# micro-xum1541.net
KiCad netlist of a schematic drawn in EAGLE
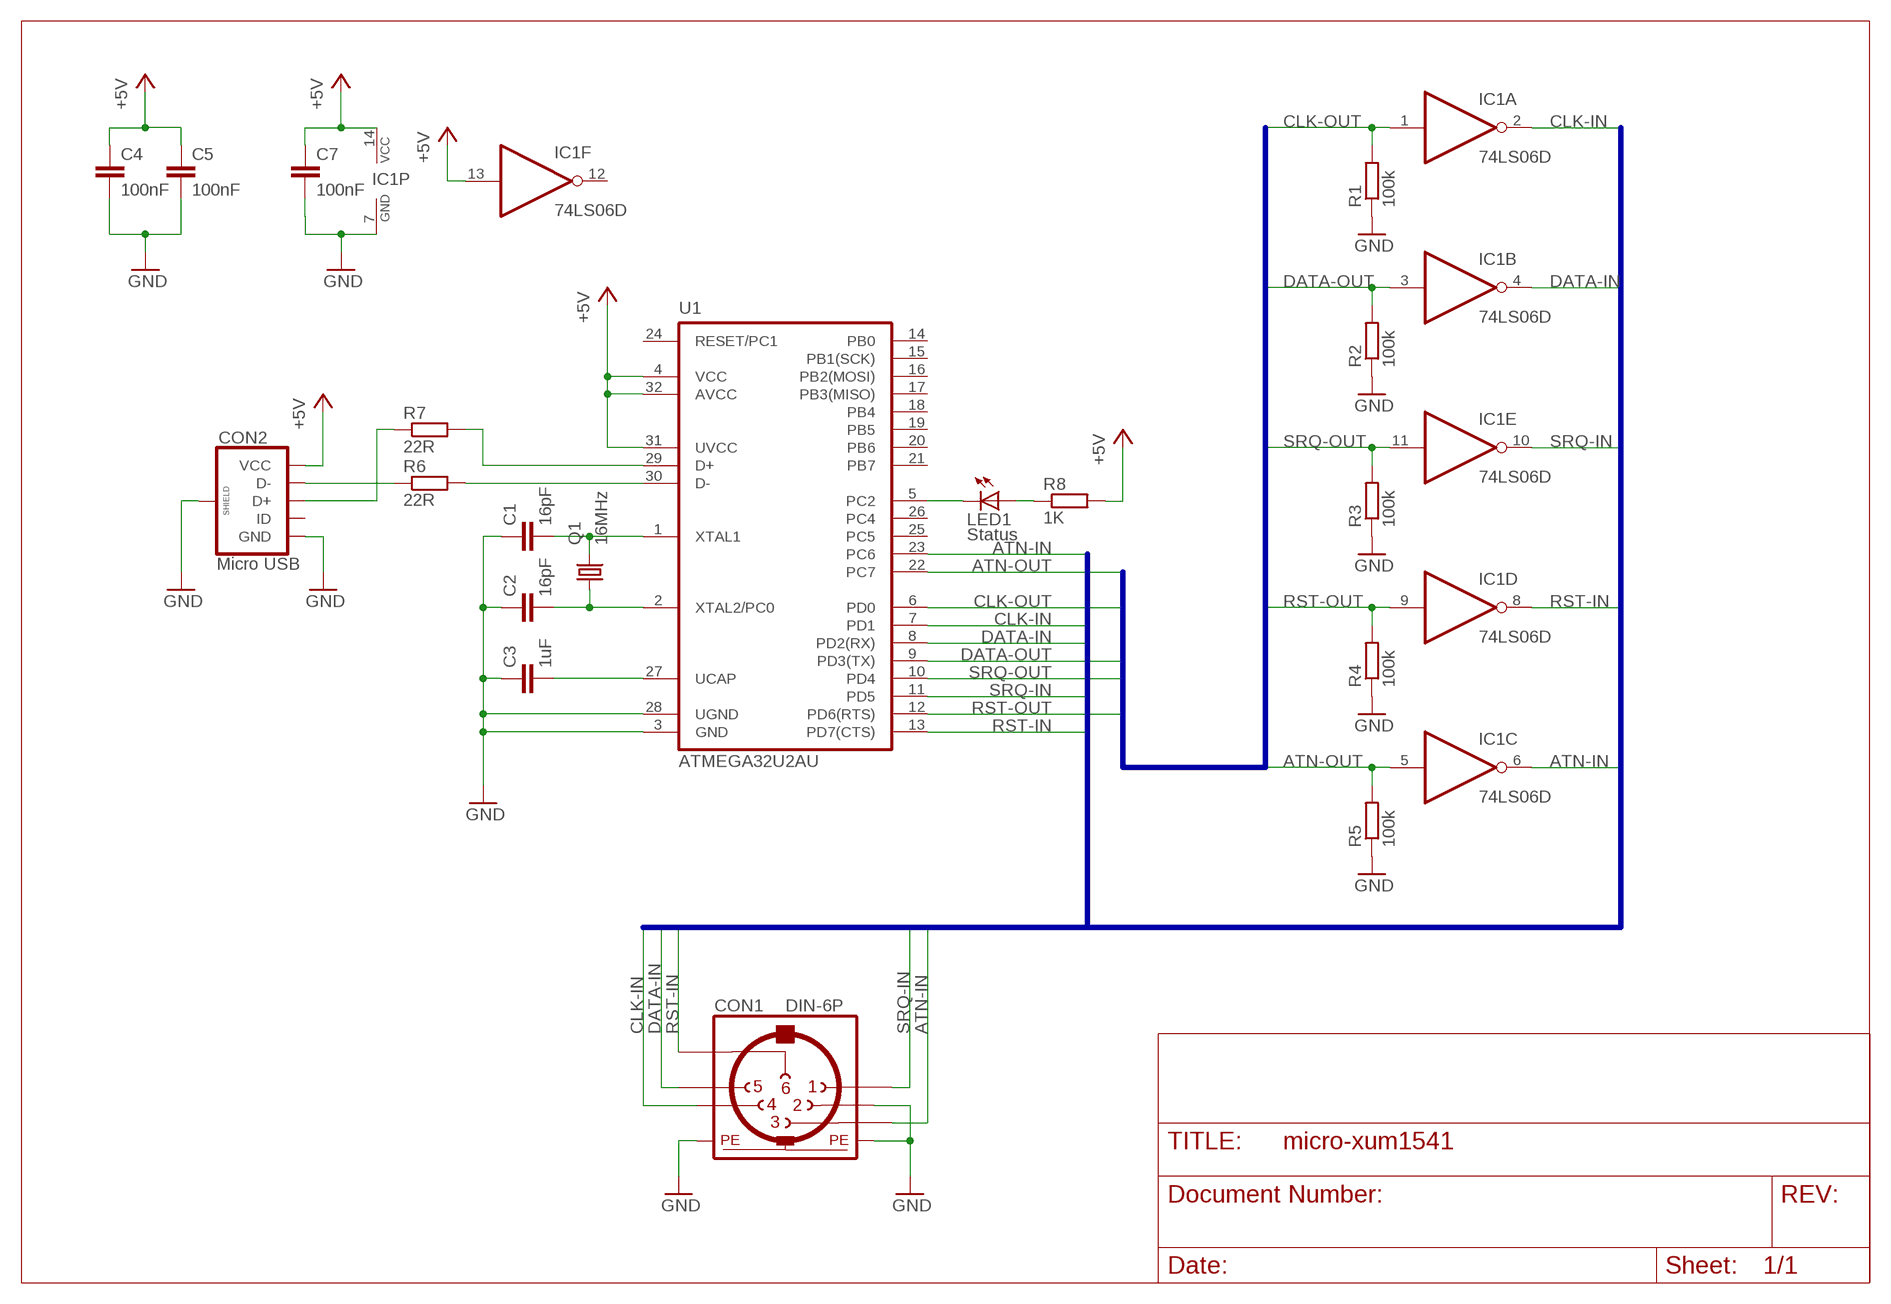
[diagram p0: schematic, sheet 1]

(export (version "E")
  (design (tool "Eeschema 10.0.6"))
  (components
    (comp (ref "C1")
      (value "16pF")
      (footprint "eagle-import:C0603K")
      (libsource (lib "eagle-import") (part "C-EUC0603K"))
    )
    (comp (ref "C2")
      (value "16pF")
      (footprint "eagle-import:C0603K")
      (libsource (lib "eagle-import") (part "C-EUC0603K"))
    )
    (comp (ref "C3")
      (value "1uF")
      (footprint "eagle-import:C0603")
      (libsource (lib "eagle-import") (part "C-EUC0603"))
    )
    (comp (ref "C4")
      (value "100nF")
      (footprint "eagle-import:C0603")
      (libsource (lib "eagle-import") (part "C-EUC0603"))
    )
    (comp (ref "C5")
      (value "100nF")
      (footprint "eagle-import:C0603")
      (libsource (lib "eagle-import") (part "C-EUC0603"))
    )
    (comp (ref "C7")
      (value "100nF")
      (footprint "eagle-import:C0603K")
      (libsource (lib "eagle-import") (part "C-EUC0603K"))
    )
    (comp (ref "CON1")
      (value "DIN-6P")
      (footprint "eagle-import:6P")
      (fields (field (name "SPICEPREFIX") "X"))
      (libsource (lib "eagle-import") (part "DIN-6P"))
    )
    (comp (ref "CON2")
      (value "Micro USB")
      (footprint "eagle-import:MICRO-USB")
      (libsource (lib "eagle-import") (part "MICRO-USB"))
    )
    (comp (ref "IC1")
      (value "74LS06D")
      (footprint "eagle-import:SO14")
      (libsource (lib "eagle-import") (part "7406DLS"))
    )
    (comp (ref "LED1")
      (value "Status")
      (footprint "eagle-import:CHIP-LED0805")
      (libsource (lib "eagle-import") (part "LEDCHIP-LED0805"))
    )
    (comp (ref "Q1")
      (value "16MHz")
      (footprint "eagle-import:2.5X2.0_KX-6")
      (libsource (lib "eagle-import") (part "KX-6"))
    )
    (comp (ref "R1")
      (value "100k")
      (footprint "eagle-import:R0603")
      (libsource (lib "eagle-import") (part "R-EU_R0603"))
    )
    (comp (ref "R2")
      (value "100k")
      (footprint "eagle-import:R0603")
      (libsource (lib "eagle-import") (part "R-EU_R0603"))
    )
    (comp (ref "R3")
      (value "100k")
      (footprint "eagle-import:R0603")
      (libsource (lib "eagle-import") (part "R-EU_R0603"))
    )
    (comp (ref "R4")
      (value "100k")
      (footprint "eagle-import:R0603")
      (libsource (lib "eagle-import") (part "R-EU_R0603"))
    )
    (comp (ref "R5")
      (value "100k")
      (footprint "eagle-import:R0603")
      (libsource (lib "eagle-import") (part "R-EU_R0603"))
    )
    (comp (ref "R6")
      (value "22R")
      (footprint "eagle-import:R0603")
      (libsource (lib "eagle-import") (part "R-EU_R0603"))
    )
    (comp (ref "R7")
      (value "22R")
      (footprint "eagle-import:R0603")
      (libsource (lib "eagle-import") (part "R-EU_R0603"))
    )
    (comp (ref "R8")
      (value "1K")
      (footprint "eagle-import:R0603")
      (libsource (lib "eagle-import") (part "R-EU_R0603"))
    )
    (comp (ref "U1")
      (value "ATMEGA32U2AU")
      (footprint "eagle-import:TQFP32")
      (fields (field (name "MPN") "ATMEGA32U2-AU"))
      (libsource (lib "eagle-import") (part "ATMEGA32U2-AUTQFP"))
    )
  )
  (nets
    (net (code "1") (name "+5V") (class "Default")
      (node (ref "C4") (pin "1") (pinfunction "1_1") (pintype "passive"))
      (node (ref "C5") (pin "1") (pinfunction "1_1") (pintype "passive"))
      (node (ref "C7") (pin "1") (pinfunction "1_1") (pintype "passive"))
      (node (ref "CON2") (pin "VBUS") (pinfunction "VCC_VBUS") (pintype "bidirectional"))
      (node (ref "IC1") (pin "13") (pinfunction "I_13") (pintype "input"))
      (node (ref "IC1") (pin "14") (pinfunction "VCC_14") (pintype "power_in"))
      (node (ref "R8") (pin "2") (pinfunction "2_2") (pintype "passive"))
      (node (ref "U1") (pin "31") (pinfunction "UVCC_31") (pintype "power_in"))
      (node (ref "U1") (pin "32") (pinfunction "AVCC_32") (pintype "power_in"))
      (node (ref "U1") (pin "4") (pinfunction "VCC_4") (pintype "power_in"))
    )
    (net (code "2") (name "/ATN-IN") (class "Default")
      (node (ref "CON1") (pin "3") (pinfunction "3_3") (pintype "passive"))
      (node (ref "IC1") (pin "6") (pinfunction "O_6") (pintype "open_collector"))
      (node (ref "U1") (pin "23") (pinfunction "PC6_23") (pintype "bidirectional"))
    )
    (net (code "3") (name "/ATN-OUT") (class "Default")
      (node (ref "IC1") (pin "5") (pinfunction "I_5") (pintype "input"))
      (node (ref "R5") (pin "2") (pinfunction "2_2") (pintype "passive"))
      (node (ref "U1") (pin "22") (pinfunction "PC7_22") (pintype "bidirectional"))
    )
    (net (code "4") (name "/CLK-IN") (class "Default")
      (node (ref "CON1") (pin "4") (pinfunction "4_4") (pintype "passive"))
      (node (ref "IC1") (pin "2") (pinfunction "O_2") (pintype "open_collector"))
      (node (ref "U1") (pin "7") (pinfunction "PD1_7") (pintype "bidirectional"))
    )
    (net (code "5") (name "/CLK-OUT") (class "Default")
      (node (ref "IC1") (pin "1") (pinfunction "I_1") (pintype "input"))
      (node (ref "R1") (pin "2") (pinfunction "2_2") (pintype "passive"))
      (node (ref "U1") (pin "6") (pinfunction "PD0_6") (pintype "bidirectional"))
    )
    (net (code "6") (name "/DATA-IN") (class "Default")
      (node (ref "CON1") (pin "5") (pinfunction "5_5") (pintype "passive"))
      (node (ref "IC1") (pin "4") (pinfunction "O_4") (pintype "open_collector"))
      (node (ref "U1") (pin "8") (pinfunction "PD2(RX)_8") (pintype "bidirectional"))
    )
    (net (code "7") (name "/DATA-OUT") (class "Default")
      (node (ref "IC1") (pin "3") (pinfunction "I_3") (pintype "input"))
      (node (ref "R2") (pin "2") (pinfunction "2_2") (pintype "passive"))
      (node (ref "U1") (pin "9") (pinfunction "PD3(TX)_9") (pintype "bidirectional"))
    )
    (net (code "8") (name "/RST-IN") (class "Default")
      (node (ref "CON1") (pin "6") (pinfunction "6_6") (pintype "passive"))
      (node (ref "IC1") (pin "8") (pinfunction "O_8") (pintype "open_collector"))
      (node (ref "U1") (pin "13") (pinfunction "PD7(CTS)_13") (pintype "bidirectional"))
    )
    (net (code "9") (name "/RST-OUT") (class "Default")
      (node (ref "IC1") (pin "9") (pinfunction "I_9") (pintype "input"))
      (node (ref "R4") (pin "2") (pinfunction "2_2") (pintype "passive"))
      (node (ref "U1") (pin "12") (pinfunction "PD6(RTS)_12") (pintype "bidirectional"))
    )
    (net (code "10") (name "/SRQ-IN") (class "Default")
      (node (ref "CON1") (pin "1") (pinfunction "1_1") (pintype "passive"))
      (node (ref "IC1") (pin "10") (pinfunction "O_10") (pintype "open_collector"))
      (node (ref "U1") (pin "11") (pinfunction "PD5_11") (pintype "bidirectional"))
    )
    (net (code "11") (name "/SRQ-OUT") (class "Default")
      (node (ref "IC1") (pin "11") (pinfunction "I_11") (pintype "input"))
      (node (ref "R3") (pin "2") (pinfunction "2_2") (pintype "passive"))
      (node (ref "U1") (pin "10") (pinfunction "PD4_10") (pintype "bidirectional"))
    )
    (net (code "12") (name "GND") (class "Default")
      (node (ref "C1") (pin "1") (pinfunction "1_1") (pintype "passive"))
      (node (ref "C2") (pin "1") (pinfunction "1_1") (pintype "passive"))
      (node (ref "C3") (pin "1") (pinfunction "1_1") (pintype "passive"))
      (node (ref "C4") (pin "2") (pinfunction "2_2") (pintype "passive"))
      (node (ref "C5") (pin "2") (pinfunction "2_2") (pintype "passive"))
      (node (ref "C7") (pin "2") (pinfunction "2_2") (pintype "passive"))
      (node (ref "CON1") (pin "2") (pinfunction "2_2") (pintype "passive"))
      (node (ref "CON1") (pin "PE1") (pinfunction "PE1_PE1") (pintype "power_in"))
      (node (ref "CON1") (pin "PE2") (pinfunction "PE2_PE2") (pintype "power_in"))
      (node (ref "CON2") (pin "GND") (pinfunction "GND_GND") (pintype "bidirectional"))
      (node (ref "CON2") (pin "SH1") (pinfunction "SHIELD_SH1") (pintype "bidirectional"))
      (node (ref "CON2") (pin "SH2") (pinfunction "SHIELD_SH2") (pintype "bidirectional"))
      (node (ref "CON2") (pin "SH3") (pinfunction "SHIELD_SH3") (pintype "bidirectional"))
      (node (ref "CON2") (pin "SH4") (pinfunction "SHIELD_SH4") (pintype "bidirectional"))
      (node (ref "IC1") (pin "7") (pinfunction "GND_7") (pintype "power_in"))
      (node (ref "R1") (pin "1") (pinfunction "1_1") (pintype "passive"))
      (node (ref "R2") (pin "1") (pinfunction "1_1") (pintype "passive"))
      (node (ref "R3") (pin "1") (pinfunction "1_1") (pintype "passive"))
      (node (ref "R4") (pin "1") (pinfunction "1_1") (pintype "passive"))
      (node (ref "R5") (pin "1") (pinfunction "1_1") (pintype "passive"))
      (node (ref "U1") (pin "28") (pinfunction "UGND_28") (pintype "passive"))
      (node (ref "U1") (pin "3") (pinfunction "GND_3") (pintype "passive"))
    )
    (net (code "13") (name "Net-(CON2-D+)") (class "Default")
      (node (ref "CON2") (pin "D+1") (pinfunction "D+_D+1") (pintype "bidirectional"))
      (node (ref "R7") (pin "1") (pinfunction "1_1") (pintype "passive"))
    )
    (net (code "14") (name "Net-(CON2-D-)") (class "Default")
      (node (ref "CON2") (pin "D-1") (pinfunction "D-_D-1") (pintype "bidirectional"))
      (node (ref "R6") (pin "1") (pinfunction "1_1") (pintype "passive"))
    )
    (net (code "15") (name "Net-(LED1-PadA)") (class "Default")
      (node (ref "LED1") (pin "A") (pinfunction "A_A") (pintype "passive"))
      (node (ref "R8") (pin "1") (pinfunction "1_1") (pintype "passive"))
    )
    (net (code "16") (name "Net-(Q1-2)") (class "Default")
      (node (ref "C1") (pin "2") (pinfunction "2_2") (pintype "passive"))
      (node (ref "Q1") (pin "3") (pinfunction "2_3") (pintype "passive"))
      (node (ref "U1") (pin "1") (pinfunction "XTAL1_1") (pintype "input"))
    )
    (net (code "17") (name "Net-(U1-D+)") (class "Default")
      (node (ref "R7") (pin "2") (pinfunction "2_2") (pintype "passive"))
      (node (ref "U1") (pin "29") (pinfunction "D+_29") (pintype "bidirectional"))
    )
    (net (code "18") (name "Net-(U1-D-)") (class "Default")
      (node (ref "R6") (pin "2") (pinfunction "2_2") (pintype "passive"))
      (node (ref "U1") (pin "30") (pinfunction "D-_30") (pintype "bidirectional"))
    )
    (net (code "19") (name "Net-(U1-PC2)") (class "Default")
      (node (ref "LED1") (pin "C") (pinfunction "C_C") (pintype "passive"))
      (node (ref "U1") (pin "5") (pinfunction "PC2_5") (pintype "bidirectional"))
    )
    (net (code "20") (name "Net-(U1-UCAP)") (class "Default")
      (node (ref "C3") (pin "2") (pinfunction "2_2") (pintype "passive"))
      (node (ref "U1") (pin "27") (pinfunction "UCAP_27") (pintype "power_in"))
    )
    (net (code "21") (name "Net-(U1-XTAL2{slash}PC0)") (class "Default")
      (node (ref "C2") (pin "2") (pinfunction "2_2") (pintype "passive"))
      (node (ref "Q1") (pin "1") (pinfunction "1_1") (pintype "passive"))
      (node (ref "U1") (pin "2") (pinfunction "XTAL2/PC0_2") (pintype "bidirectional"))
    )
    (net (code "22") (name "unconnected-(CON2-ID-PadID1)") (class "Default")
      (node (ref "CON2") (pin "ID1") (pinfunction "ID_ID1") (pintype "bidirectional"))
    )
    (net (code "23") (name "unconnected-(IC1F-O-Pad12)") (class "Default")
      (node (ref "IC1") (pin "12") (pinfunction "O_12") (pintype "open_collector"))
    )
    (net (code "24") (name "unconnected-(U1-PB0-Pad14)") (class "Default")
      (node (ref "U1") (pin "14") (pinfunction "PB0_14") (pintype "bidirectional"))
    )
    (net (code "25") (name "unconnected-(U1-PB1(SCK)-Pad15)") (class "Default")
      (node (ref "U1") (pin "15") (pinfunction "PB1(SCK)_15") (pintype "bidirectional"))
    )
    (net (code "26") (name "unconnected-(U1-PB2(MOSI)-Pad16)") (class "Default")
      (node (ref "U1") (pin "16") (pinfunction "PB2(MOSI)_16") (pintype "bidirectional"))
    )
    (net (code "27") (name "unconnected-(U1-PB3(MISO)-Pad17)") (class "Default")
      (node (ref "U1") (pin "17") (pinfunction "PB3(MISO)_17") (pintype "bidirectional"))
    )
    (net (code "28") (name "unconnected-(U1-PB4-Pad18)") (class "Default")
      (node (ref "U1") (pin "18") (pinfunction "PB4_18") (pintype "bidirectional"))
    )
    (net (code "29") (name "unconnected-(U1-PB5-Pad19)") (class "Default")
      (node (ref "U1") (pin "19") (pinfunction "PB5_19") (pintype "bidirectional"))
    )
    (net (code "30") (name "unconnected-(U1-PB6-Pad20)") (class "Default")
      (node (ref "U1") (pin "20") (pinfunction "PB6_20") (pintype "bidirectional"))
    )
    (net (code "31") (name "unconnected-(U1-PB7-Pad21)") (class "Default")
      (node (ref "U1") (pin "21") (pinfunction "PB7_21") (pintype "bidirectional"))
    )
    (net (code "32") (name "unconnected-(U1-PC4-Pad26)") (class "Default")
      (node (ref "U1") (pin "26") (pinfunction "PC4_26") (pintype "bidirectional"))
    )
    (net (code "33") (name "unconnected-(U1-PC5-Pad25)") (class "Default")
      (node (ref "U1") (pin "25") (pinfunction "PC5_25") (pintype "bidirectional"))
    )
    (net (code "34") (name "unconnected-(U1-RESET{slash}PC1-Pad24)") (class "Default")
      (node (ref "U1") (pin "24") (pinfunction "RESET/PC1_24") (pintype "bidirectional"))
    )
  )
)
